# Amplified-Mic-Electret.net
KiCad netlist of a schematic drawn in EAGLE
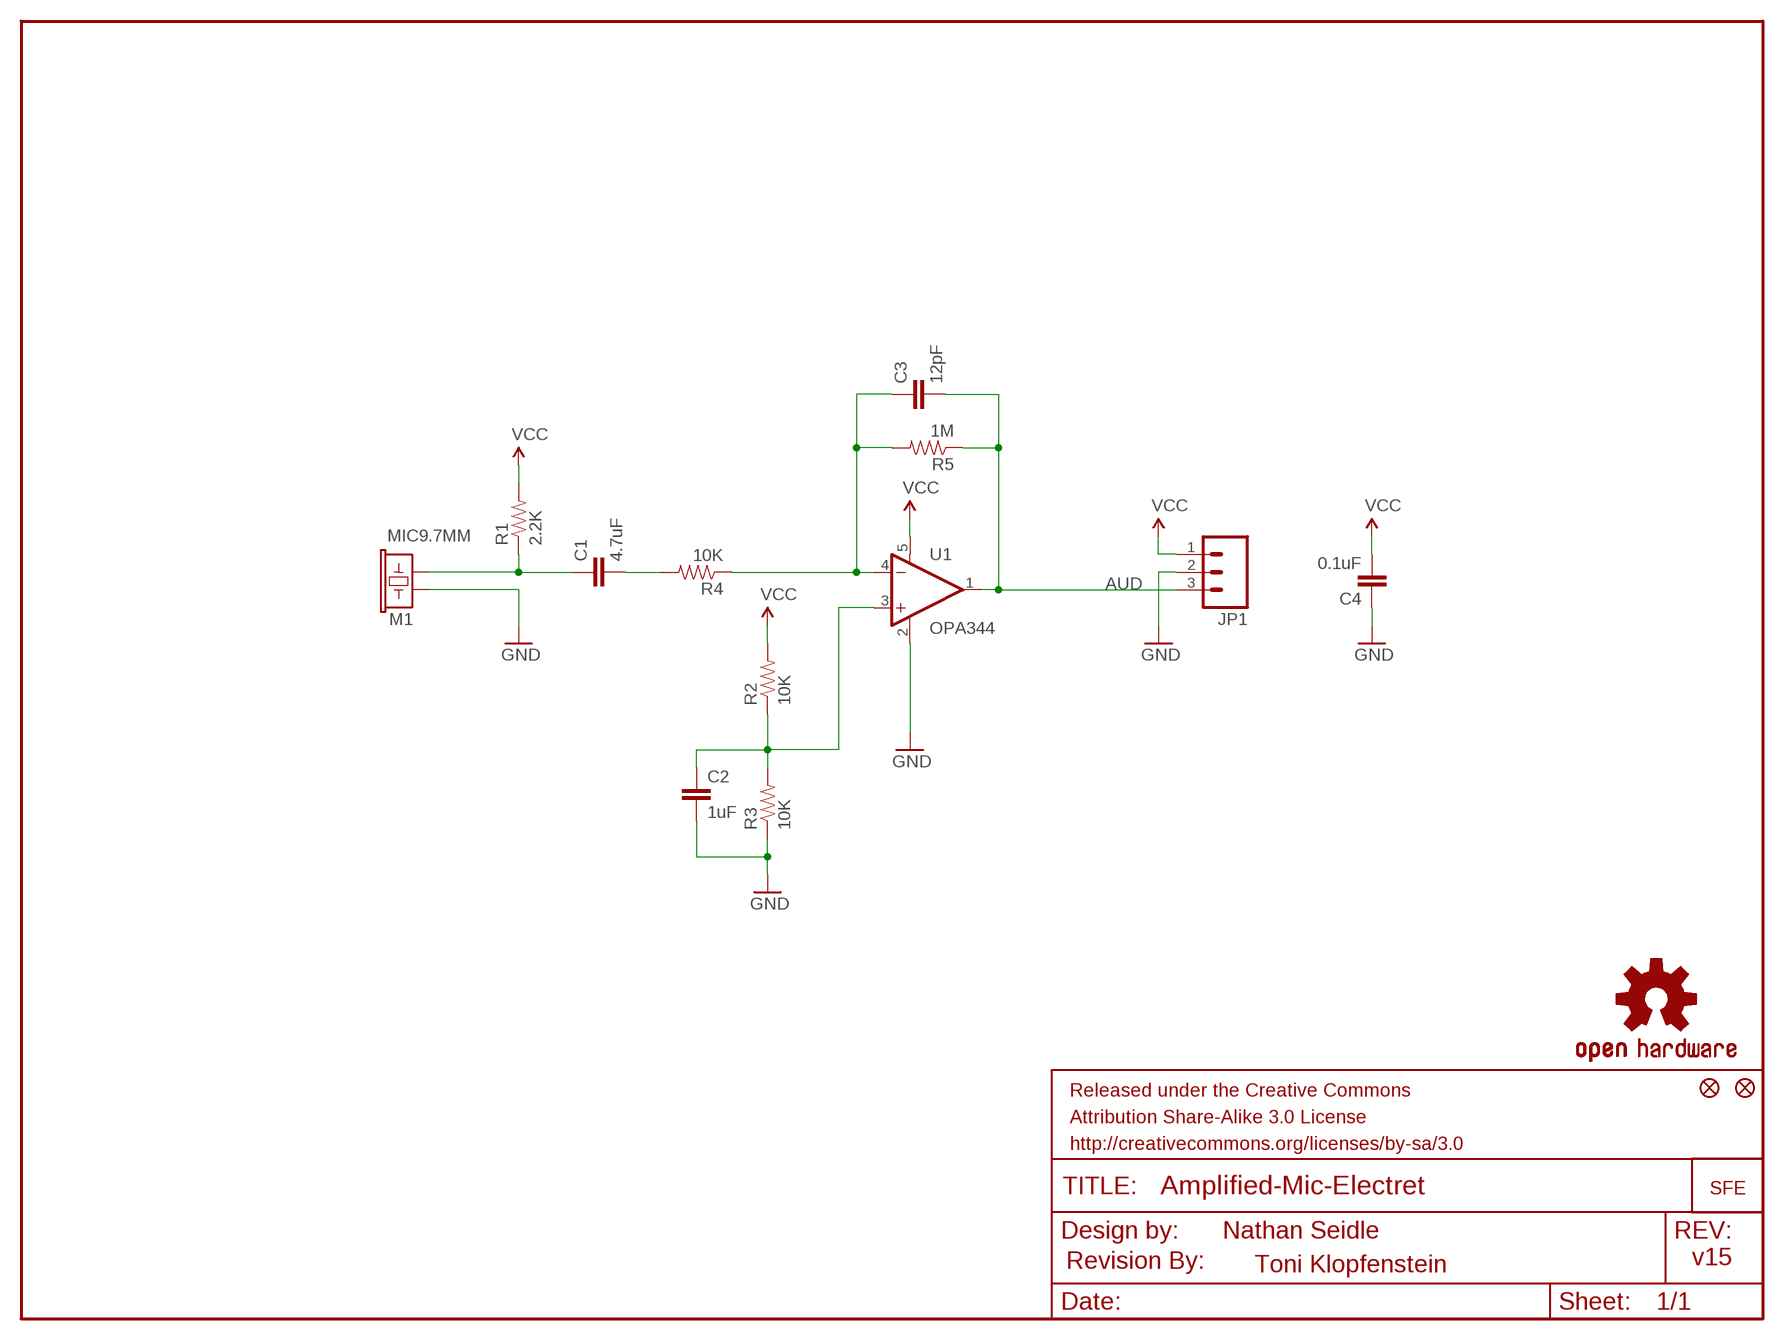
[diagram p0: schematic, sheet 1]

(export (version "E")
  (design (tool "Eeschema 10.0.6"))
  (components
    (comp (ref "C1")
      (value "4.7uF")
      (footprint "eagle-import:0603-CAP")
      (libsource (lib "eagle-import") (part "4.7UF-6.3V-10%(0603)0603"))
    )
    (comp (ref "C2")
      (value "1uF")
      (footprint "eagle-import:0603-CAP")
      (libsource (lib "eagle-import") (part "1.0UF-16V-10%(0603)"))
    )
    (comp (ref "C3")
      (value "12pF")
      (footprint "eagle-import:0603-CAP")
      (libsource (lib "eagle-import") (part "12PF-50V-5%(0603)"))
    )
    (comp (ref "C4")
      (value "0.1uF")
      (footprint "eagle-import:0603-CAP")
      (libsource (lib "eagle-import") (part "0.1UF-25V(+80/-20%)(0603)"))
    )
    (comp (ref "FRAME1")
      (value "FRAME-LETTER")
      (footprint "eagle-import:CREATIVE_COMMONS")
      (libsource (lib "eagle-import") (part "FRAME-LETTER"))
    )
    (comp (ref "JP1")
      (value "M03PTH")
      (footprint "eagle-import:1X03")
      (libsource (lib "eagle-import") (part "M03PTH"))
    )
    (comp (ref "JP2")
      (value "FIDUCIAL1X2")
      (footprint "eagle-import:FIDUCIAL-1X2")
      (libsource (lib "eagle-import") (part "FIDUCIAL1X2"))
    )
    (comp (ref "JP3")
      (value "FIDUCIAL1X2")
      (footprint "eagle-import:FIDUCIAL-1X2")
      (libsource (lib "eagle-import") (part "FIDUCIAL1X2"))
    )
    (comp (ref "LOGO1")
      (value "OSHW-LOGOS")
      (footprint "eagle-import:OSHW-LOGO-S")
      (libsource (lib "eagle-import") (part "OSHW-LOGOS"))
    )
    (comp (ref "M1")
      (value "MIC9.7MM")
      (footprint "eagle-import:MIC-9.7MM")
      (libsource (lib "eagle-import") (part "MIC9.7MM"))
    )
    (comp (ref "R1")
      (value "2.2K")
      (footprint "eagle-import:0603-RES")
      (libsource (lib "eagle-import") (part "2.2KOHM1/10W1%(0603)"))
    )
    (comp (ref "R2")
      (value "10K")
      (footprint "eagle-import:0603-RES")
      (libsource (lib "eagle-import") (part "10KOHM1/10W1%(0603)0603"))
    )
    (comp (ref "R3")
      (value "10K")
      (footprint "eagle-import:0603-RES")
      (libsource (lib "eagle-import") (part "10KOHM1/10W1%(0603)0603"))
    )
    (comp (ref "R4")
      (value "10K")
      (footprint "eagle-import:0603-RES")
      (libsource (lib "eagle-import") (part "10KOHM1/10W1%(0603)0603"))
    )
    (comp (ref "R5")
      (value "1M")
      (footprint "eagle-import:0603-RES")
      (libsource (lib "eagle-import") (part "1MOHM1/10W1%(0603)"))
    )
    (comp (ref "U$1")
      (value "LOGO-SFESK")
      (footprint "eagle-import:SFE-LOGO-FLAME")
      (libsource (lib "eagle-import") (part "LOGO-SFESK"))
    )
    (comp (ref "U$2")
      (value "REVISION")
      (footprint "eagle-import:REVISION")
      (libsource (lib "eagle-import") (part "REVISION"))
    )
    (comp (ref "U1")
      (value "OPA344")
      (footprint "eagle-import:SOT23-5")
      (libsource (lib "eagle-import") (part "OPA344"))
    )
  )
  (nets
    (net (code "1") (name "/AUD") (class "Default")
      (node (ref "C3") (pin "2") (pinfunction "2_2") (pintype "passive"))
      (node (ref "JP1") (pin "3") (pinfunction "3_3") (pintype "passive"))
      (node (ref "R5") (pin "1") (pinfunction "1_1") (pintype "passive"))
      (node (ref "U1") (pin "1") (pinfunction "OUT_1") (pintype "output"))
    )
    (net (code "2") (name "GND") (class "Default")
      (node (ref "C2") (pin "2") (pinfunction "2_2") (pintype "passive"))
      (node (ref "C4") (pin "1") (pinfunction "1_1") (pintype "passive"))
      (node (ref "JP1") (pin "2") (pinfunction "2_2") (pintype "passive"))
      (node (ref "M1") (pin "2") (pinfunction "2_2") (pintype "passive"))
      (node (ref "R3") (pin "1") (pinfunction "1_1") (pintype "passive"))
      (node (ref "U1") (pin "2") (pinfunction "V-_2") (pintype "power_in"))
    )
    (net (code "3") (name "Net-(C1-Pad1)") (class "Default")
      (node (ref "C1") (pin "1") (pinfunction "1_1") (pintype "passive"))
      (node (ref "M1") (pin "1") (pinfunction "1_1") (pintype "passive"))
      (node (ref "R1") (pin "1") (pinfunction "1_1") (pintype "passive"))
    )
    (net (code "4") (name "Net-(C1-Pad2)") (class "Default")
      (node (ref "C1") (pin "2") (pinfunction "2_2") (pintype "passive"))
      (node (ref "R4") (pin "2") (pinfunction "2_2") (pintype "passive"))
    )
    (net (code "5") (name "Net-(U1-+IN)") (class "Default")
      (node (ref "C2") (pin "1") (pinfunction "1_1") (pintype "passive"))
      (node (ref "R2") (pin "1") (pinfunction "1_1") (pintype "passive"))
      (node (ref "R3") (pin "2") (pinfunction "2_2") (pintype "passive"))
      (node (ref "U1") (pin "3") (pinfunction "+IN_3") (pintype "input"))
    )
    (net (code "6") (name "Net-(U1--IN)") (class "Default")
      (node (ref "C3") (pin "1") (pinfunction "1_1") (pintype "passive"))
      (node (ref "R4") (pin "1") (pinfunction "1_1") (pintype "passive"))
      (node (ref "R5") (pin "2") (pinfunction "2_2") (pintype "passive"))
      (node (ref "U1") (pin "4") (pinfunction "-IN_4") (pintype "input"))
    )
    (net (code "7") (name "VCC") (class "Default")
      (node (ref "C4") (pin "2") (pinfunction "2_2") (pintype "passive"))
      (node (ref "JP1") (pin "1") (pinfunction "1_1") (pintype "passive"))
      (node (ref "R1") (pin "2") (pinfunction "2_2") (pintype "passive"))
      (node (ref "R2") (pin "2") (pinfunction "2_2") (pintype "passive"))
      (node (ref "U1") (pin "5") (pinfunction "V+_5") (pintype "power_in"))
    )
  )
)
